# ax8052f143_mit_antenne.net
KiCad netlist of a schematic drawn in EAGLE
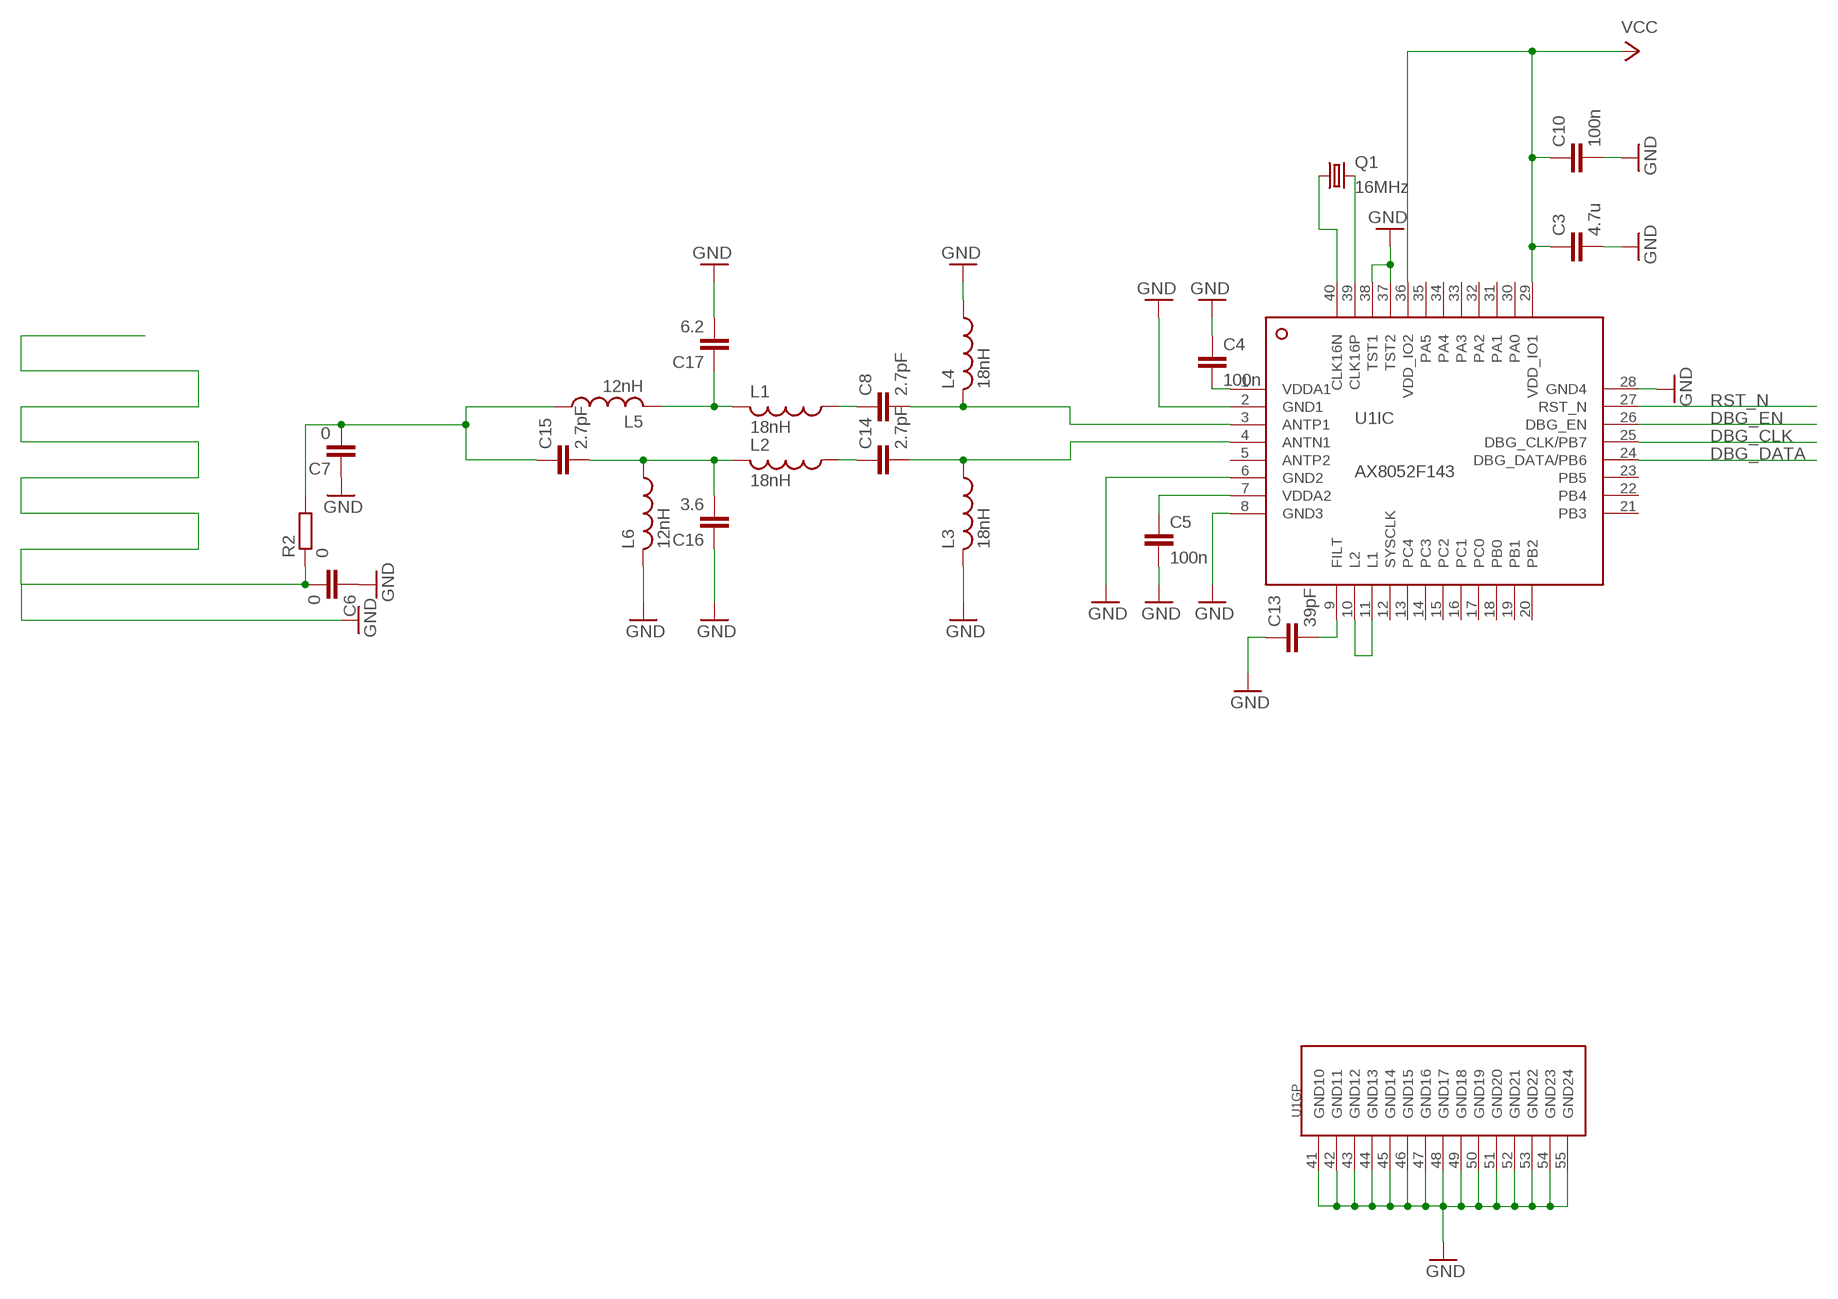
[diagram p0: schematic, sheet 1]

(export (version "E")
  (design (tool "Eeschema 10.0.6"))
  (components
    (comp (ref "C3")
      (value "4.7u")
      (footprint "eagle-import:C0805")
      (libsource (lib "eagle-import") (part "C-EUC0805"))
    )
    (comp (ref "C4")
      (value "100n")
      (footprint "eagle-import:C0603")
      (libsource (lib "eagle-import") (part "C-EUC0603"))
    )
    (comp (ref "C5")
      (value "100n")
      (footprint "eagle-import:C0603")
      (libsource (lib "eagle-import") (part "C-EUC0603"))
    )
    (comp (ref "C6")
      (value "0")
      (footprint "eagle-import:C0805")
      (libsource (lib "eagle-import") (part "C-EUC0805"))
    )
    (comp (ref "C7")
      (value "0")
      (footprint "eagle-import:C0805")
      (libsource (lib "eagle-import") (part "C-EUC0805"))
    )
    (comp (ref "C8")
      (value "2.7pF")
      (footprint "eagle-import:C0805")
      (libsource (lib "eagle-import") (part "C-EUC0805"))
    )
    (comp (ref "C10")
      (value "100n")
      (footprint "eagle-import:C0603")
      (libsource (lib "eagle-import") (part "C-EUC0603"))
    )
    (comp (ref "C13")
      (value "39pF")
      (footprint "eagle-import:C0805")
      (libsource (lib "eagle-import") (part "C-EUC0805"))
    )
    (comp (ref "C14")
      (value "2.7pF")
      (footprint "eagle-import:C0805")
      (libsource (lib "eagle-import") (part "C-EUC0805"))
    )
    (comp (ref "C15")
      (value "2.7pF")
      (footprint "eagle-import:C0805")
      (libsource (lib "eagle-import") (part "C-EUC0805"))
    )
    (comp (ref "C16")
      (value "3.6")
      (footprint "eagle-import:C0805")
      (libsource (lib "eagle-import") (part "C-EUC0805"))
    )
    (comp (ref "C17")
      (value "6.2")
      (footprint "eagle-import:C0805")
      (libsource (lib "eagle-import") (part "C-EUC0805"))
    )
    (comp (ref "L1")
      (value "18nH")
      (footprint "eagle-import:C0603")
      (libsource (lib "eagle-import") (part "L-US0603"))
    )
    (comp (ref "L2")
      (value "18nH")
      (footprint "eagle-import:C0603")
      (libsource (lib "eagle-import") (part "L-US0603"))
    )
    (comp (ref "L3")
      (value "18nH")
      (footprint "eagle-import:C0603")
      (libsource (lib "eagle-import") (part "L-US0603"))
    )
    (comp (ref "L4")
      (value "18nH")
      (footprint "eagle-import:C0603")
      (libsource (lib "eagle-import") (part "L-US0603"))
    )
    (comp (ref "L5")
      (value "12nH")
      (footprint "eagle-import:C0603")
      (libsource (lib "eagle-import") (part "L-US0603"))
    )
    (comp (ref "L6")
      (value "12nH")
      (footprint "eagle-import:C0603")
      (libsource (lib "eagle-import") (part "L-US0603"))
    )
    (comp (ref "Q1")
      (value "16MHz")
      (footprint "eagle-import:SM49")
      (libsource (lib "eagle-import") (part "CRYSTALSM49"))
    )
    (comp (ref "R2")
      (value "0")
      (footprint "eagle-import:R0603")
      (libsource (lib "eagle-import") (part "R-EU_R0603"))
    )
    (comp (ref "U1")
      (value "AX8052F143HS")
      (footprint "eagle-import:QFN40-H")
      (libsource (lib "eagle-import") (part "AX8052F143HS"))
    )
  )
  (nets
    (net (code "1") (name "/DBG_CLK") (class "Default")
      (node (ref "U1") (pin "25") (pinfunction "DBG_CLK/PB7_25") (pintype "bidirectional"))
    )
    (net (code "2") (name "/DBG_DATA") (class "Default")
      (node (ref "U1") (pin "24") (pinfunction "DBG_DATA/PB6_24") (pintype "bidirectional"))
    )
    (net (code "3") (name "/DBG_EN") (class "Default")
      (node (ref "U1") (pin "26") (pinfunction "DBG_EN_26") (pintype "input"))
    )
    (net (code "4") (name "/RST_N") (class "Default")
      (node (ref "U1") (pin "27") (pinfunction "RST_N_27") (pintype "input"))
    )
    (net (code "5") (name "GND") (class "Default")
      (node (ref "C10") (pin "2") (pinfunction "2_2") (pintype "passive"))
      (node (ref "C13") (pin "1") (pinfunction "1_1") (pintype "passive"))
      (node (ref "C16") (pin "1") (pinfunction "1_1") (pintype "passive"))
      (node (ref "C17") (pin "2") (pinfunction "2_2") (pintype "passive"))
      (node (ref "C3") (pin "2") (pinfunction "2_2") (pintype "passive"))
      (node (ref "C4") (pin "1") (pinfunction "1_1") (pintype "passive"))
      (node (ref "C5") (pin "2") (pinfunction "2_2") (pintype "passive"))
      (node (ref "C6") (pin "1") (pinfunction "1_1") (pintype "passive"))
      (node (ref "C6") (pin "2") (pinfunction "2_2") (pintype "passive"))
      (node (ref "C7") (pin "1") (pinfunction "1_1") (pintype "passive"))
      (node (ref "L3") (pin "2") (pinfunction "2_2") (pintype "passive"))
      (node (ref "L4") (pin "1") (pinfunction "1_1") (pintype "passive"))
      (node (ref "L6") (pin "2") (pinfunction "2_2") (pintype "passive"))
      (node (ref "R2") (pin "1") (pinfunction "1_1") (pintype "passive"))
      (node (ref "U1") (pin "2") (pinfunction "GND1_2") (pintype "power_in"))
      (node (ref "U1") (pin "28") (pinfunction "GND4_28") (pintype "power_in"))
      (node (ref "U1") (pin "37") (pinfunction "TST2_37") (pintype "bidirectional"))
      (node (ref "U1") (pin "38") (pinfunction "TST1_38") (pintype "power_in"))
      (node (ref "U1") (pin "41") (pinfunction "GND10_41") (pintype "power_in"))
      (node (ref "U1") (pin "42") (pinfunction "GND11_42") (pintype "power_in"))
      (node (ref "U1") (pin "43") (pinfunction "GND12_43") (pintype "power_in"))
      (node (ref "U1") (pin "44") (pinfunction "GND13_44") (pintype "power_in"))
      (node (ref "U1") (pin "45") (pinfunction "GND14_45") (pintype "power_in"))
      (node (ref "U1") (pin "46") (pinfunction "GND15_46") (pintype "power_in"))
      (node (ref "U1") (pin "47") (pinfunction "GND16_47") (pintype "power_in"))
      (node (ref "U1") (pin "48") (pinfunction "GND17_48") (pintype "power_in"))
      (node (ref "U1") (pin "49") (pinfunction "GND18_49") (pintype "power_in"))
      (node (ref "U1") (pin "50") (pinfunction "GND19_50") (pintype "power_in"))
      (node (ref "U1") (pin "51") (pinfunction "GND20_51") (pintype "power_in"))
      (node (ref "U1") (pin "52") (pinfunction "GND21_52") (pintype "power_in"))
      (node (ref "U1") (pin "53") (pinfunction "GND22_53") (pintype "power_in"))
      (node (ref "U1") (pin "54") (pinfunction "GND23_54") (pintype "power_in"))
      (node (ref "U1") (pin "55") (pinfunction "GND24_55") (pintype "power_in"))
      (node (ref "U1") (pin "6") (pinfunction "GND2_6") (pintype "passive"))
      (node (ref "U1") (pin "8") (pinfunction "GND3_8") (pintype "power_in"))
    )
    (net (code "6") (name "Net-(C8-Pad1)") (class "Default")
      (node (ref "C8") (pin "1") (pinfunction "1_1") (pintype "passive"))
      (node (ref "L1") (pin "1") (pinfunction "1_1") (pintype "passive"))
    )
    (net (code "7") (name "Net-(C14-Pad1)") (class "Default")
      (node (ref "C14") (pin "1") (pinfunction "1_1") (pintype "passive"))
      (node (ref "L2") (pin "1") (pinfunction "1_1") (pintype "passive"))
    )
    (net (code "8") (name "Net-(C15-Pad1)") (class "Default")
      (node (ref "C15") (pin "1") (pinfunction "1_1") (pintype "passive"))
      (node (ref "C7") (pin "2") (pinfunction "2_2") (pintype "passive"))
      (node (ref "L5") (pin "1") (pinfunction "1_1") (pintype "passive"))
      (node (ref "R2") (pin "2") (pinfunction "2_2") (pintype "passive"))
    )
    (net (code "9") (name "Net-(C15-Pad2)") (class "Default")
      (node (ref "C15") (pin "2") (pinfunction "2_2") (pintype "passive"))
      (node (ref "C16") (pin "2") (pinfunction "2_2") (pintype "passive"))
      (node (ref "L2") (pin "2") (pinfunction "2_2") (pintype "passive"))
      (node (ref "L6") (pin "1") (pinfunction "1_1") (pintype "passive"))
    )
    (net (code "10") (name "Net-(C17-Pad1)") (class "Default")
      (node (ref "C17") (pin "1") (pinfunction "1_1") (pintype "passive"))
      (node (ref "L1") (pin "2") (pinfunction "2_2") (pintype "passive"))
      (node (ref "L5") (pin "2") (pinfunction "2_2") (pintype "passive"))
    )
    (net (code "11") (name "Net-(U1B-ANTN1)") (class "Default")
      (node (ref "C14") (pin "2") (pinfunction "2_2") (pintype "passive"))
      (node (ref "L3") (pin "1") (pinfunction "1_1") (pintype "passive"))
      (node (ref "U1") (pin "4") (pinfunction "ANTN1_4") (pintype "power_in"))
    )
    (net (code "12") (name "Net-(U1B-ANTP1)") (class "Default")
      (node (ref "C8") (pin "2") (pinfunction "2_2") (pintype "passive"))
      (node (ref "L4") (pin "2") (pinfunction "2_2") (pintype "passive"))
      (node (ref "U1") (pin "3") (pinfunction "ANTP1_3") (pintype "power_in"))
    )
    (net (code "13") (name "Net-(U1B-CLK16N)") (class "Default")
      (node (ref "Q1") (pin "1") (pinfunction "1_1") (pintype "passive"))
      (node (ref "U1") (pin "40") (pinfunction "CLK16N_40") (pintype "passive"))
    )
    (net (code "14") (name "Net-(U1B-CLK16P)") (class "Default")
      (node (ref "Q1") (pin "2") (pinfunction "2_2") (pintype "passive"))
      (node (ref "U1") (pin "39") (pinfunction "CLK16P_39") (pintype "passive"))
    )
    (net (code "15") (name "Net-(U1B-FILT)") (class "Default")
      (node (ref "C13") (pin "2") (pinfunction "2_2") (pintype "passive"))
      (node (ref "U1") (pin "9") (pinfunction "FILT_9") (pintype "passive"))
    )
    (net (code "16") (name "Net-(U1B-L1)") (class "Default")
      (node (ref "U1") (pin "10") (pinfunction "L2_10") (pintype "passive"))
      (node (ref "U1") (pin "11") (pinfunction "L1_11") (pintype "input"))
    )
    (net (code "17") (name "Net-(U1B-VDDA1)") (class "Default")
      (node (ref "C4") (pin "2") (pinfunction "2_2") (pintype "passive"))
      (node (ref "U1") (pin "1") (pinfunction "VDDA1_1") (pintype "power_in"))
    )
    (net (code "18") (name "Net-(U1B-VDDA2)") (class "Default")
      (node (ref "C5") (pin "1") (pinfunction "1_1") (pintype "passive"))
      (node (ref "U1") (pin "7") (pinfunction "VDDA2_7") (pintype "power_in"))
    )
    (net (code "19") (name "VCC") (class "Default")
      (node (ref "C10") (pin "1") (pinfunction "1_1") (pintype "passive"))
      (node (ref "C3") (pin "1") (pinfunction "1_1") (pintype "passive"))
      (node (ref "U1") (pin "29") (pinfunction "VDD_IO1_29") (pintype "power_in"))
      (node (ref "U1") (pin "36") (pinfunction "VDD_IO2_36") (pintype "bidirectional"))
    )
    (net (code "20") (name "unconnected-(U1B-ANTP2-Pad5)") (class "Default")
      (node (ref "U1") (pin "5") (pinfunction "ANTP2_5") (pintype "passive"))
    )
    (net (code "21") (name "unconnected-(U1B-PA0-Pad30)") (class "Default")
      (node (ref "U1") (pin "30") (pinfunction "PA0_30") (pintype "bidirectional"))
    )
    (net (code "22") (name "unconnected-(U1B-PA1-Pad31)") (class "Default")
      (node (ref "U1") (pin "31") (pinfunction "PA1_31") (pintype "bidirectional"))
    )
    (net (code "23") (name "unconnected-(U1B-PA2-Pad32)") (class "Default")
      (node (ref "U1") (pin "32") (pinfunction "PA2_32") (pintype "bidirectional"))
    )
    (net (code "24") (name "unconnected-(U1B-PA3-Pad33)") (class "Default")
      (node (ref "U1") (pin "33") (pinfunction "PA3_33") (pintype "bidirectional"))
    )
    (net (code "25") (name "unconnected-(U1B-PA4-Pad34)") (class "Default")
      (node (ref "U1") (pin "34") (pinfunction "PA4_34") (pintype "bidirectional"))
    )
    (net (code "26") (name "unconnected-(U1B-PA5-Pad35)") (class "Default")
      (node (ref "U1") (pin "35") (pinfunction "PA5_35") (pintype "bidirectional"))
    )
    (net (code "27") (name "unconnected-(U1B-PB0-Pad18)") (class "Default")
      (node (ref "U1") (pin "18") (pinfunction "PB0_18") (pintype "bidirectional"))
    )
    (net (code "28") (name "unconnected-(U1B-PB1-Pad19)") (class "Default")
      (node (ref "U1") (pin "19") (pinfunction "PB1_19") (pintype "bidirectional"))
    )
    (net (code "29") (name "unconnected-(U1B-PB2-Pad20)") (class "Default")
      (node (ref "U1") (pin "20") (pinfunction "PB2_20") (pintype "bidirectional"))
    )
    (net (code "30") (name "unconnected-(U1B-PB3-Pad21)") (class "Default")
      (node (ref "U1") (pin "21") (pinfunction "PB3_21") (pintype "bidirectional"))
    )
    (net (code "31") (name "unconnected-(U1B-PB4-Pad22)") (class "Default")
      (node (ref "U1") (pin "22") (pinfunction "PB4_22") (pintype "bidirectional"))
    )
    (net (code "32") (name "unconnected-(U1B-PB5-Pad23)") (class "Default")
      (node (ref "U1") (pin "23") (pinfunction "PB5_23") (pintype "bidirectional"))
    )
    (net (code "33") (name "unconnected-(U1B-PC0-Pad17)") (class "Default")
      (node (ref "U1") (pin "17") (pinfunction "PC0_17") (pintype "bidirectional"))
    )
    (net (code "34") (name "unconnected-(U1B-PC1-Pad16)") (class "Default")
      (node (ref "U1") (pin "16") (pinfunction "PC1_16") (pintype "bidirectional"))
    )
    (net (code "35") (name "unconnected-(U1B-PC2-Pad15)") (class "Default")
      (node (ref "U1") (pin "15") (pinfunction "PC2_15") (pintype "bidirectional"))
    )
    (net (code "36") (name "unconnected-(U1B-PC3-Pad14)") (class "Default")
      (node (ref "U1") (pin "14") (pinfunction "PC3_14") (pintype "bidirectional"))
    )
    (net (code "37") (name "unconnected-(U1B-PC4-Pad13)") (class "Default")
      (node (ref "U1") (pin "13") (pinfunction "PC4_13") (pintype "bidirectional"))
    )
    (net (code "38") (name "unconnected-(U1B-SYSCLK-Pad12)") (class "Default")
      (node (ref "U1") (pin "12") (pinfunction "SYSCLK_12") (pintype "output"))
    )
  )
)
